# SwitchRouter2x3c.net
KiCad netlist of a schematic drawn in EAGLE
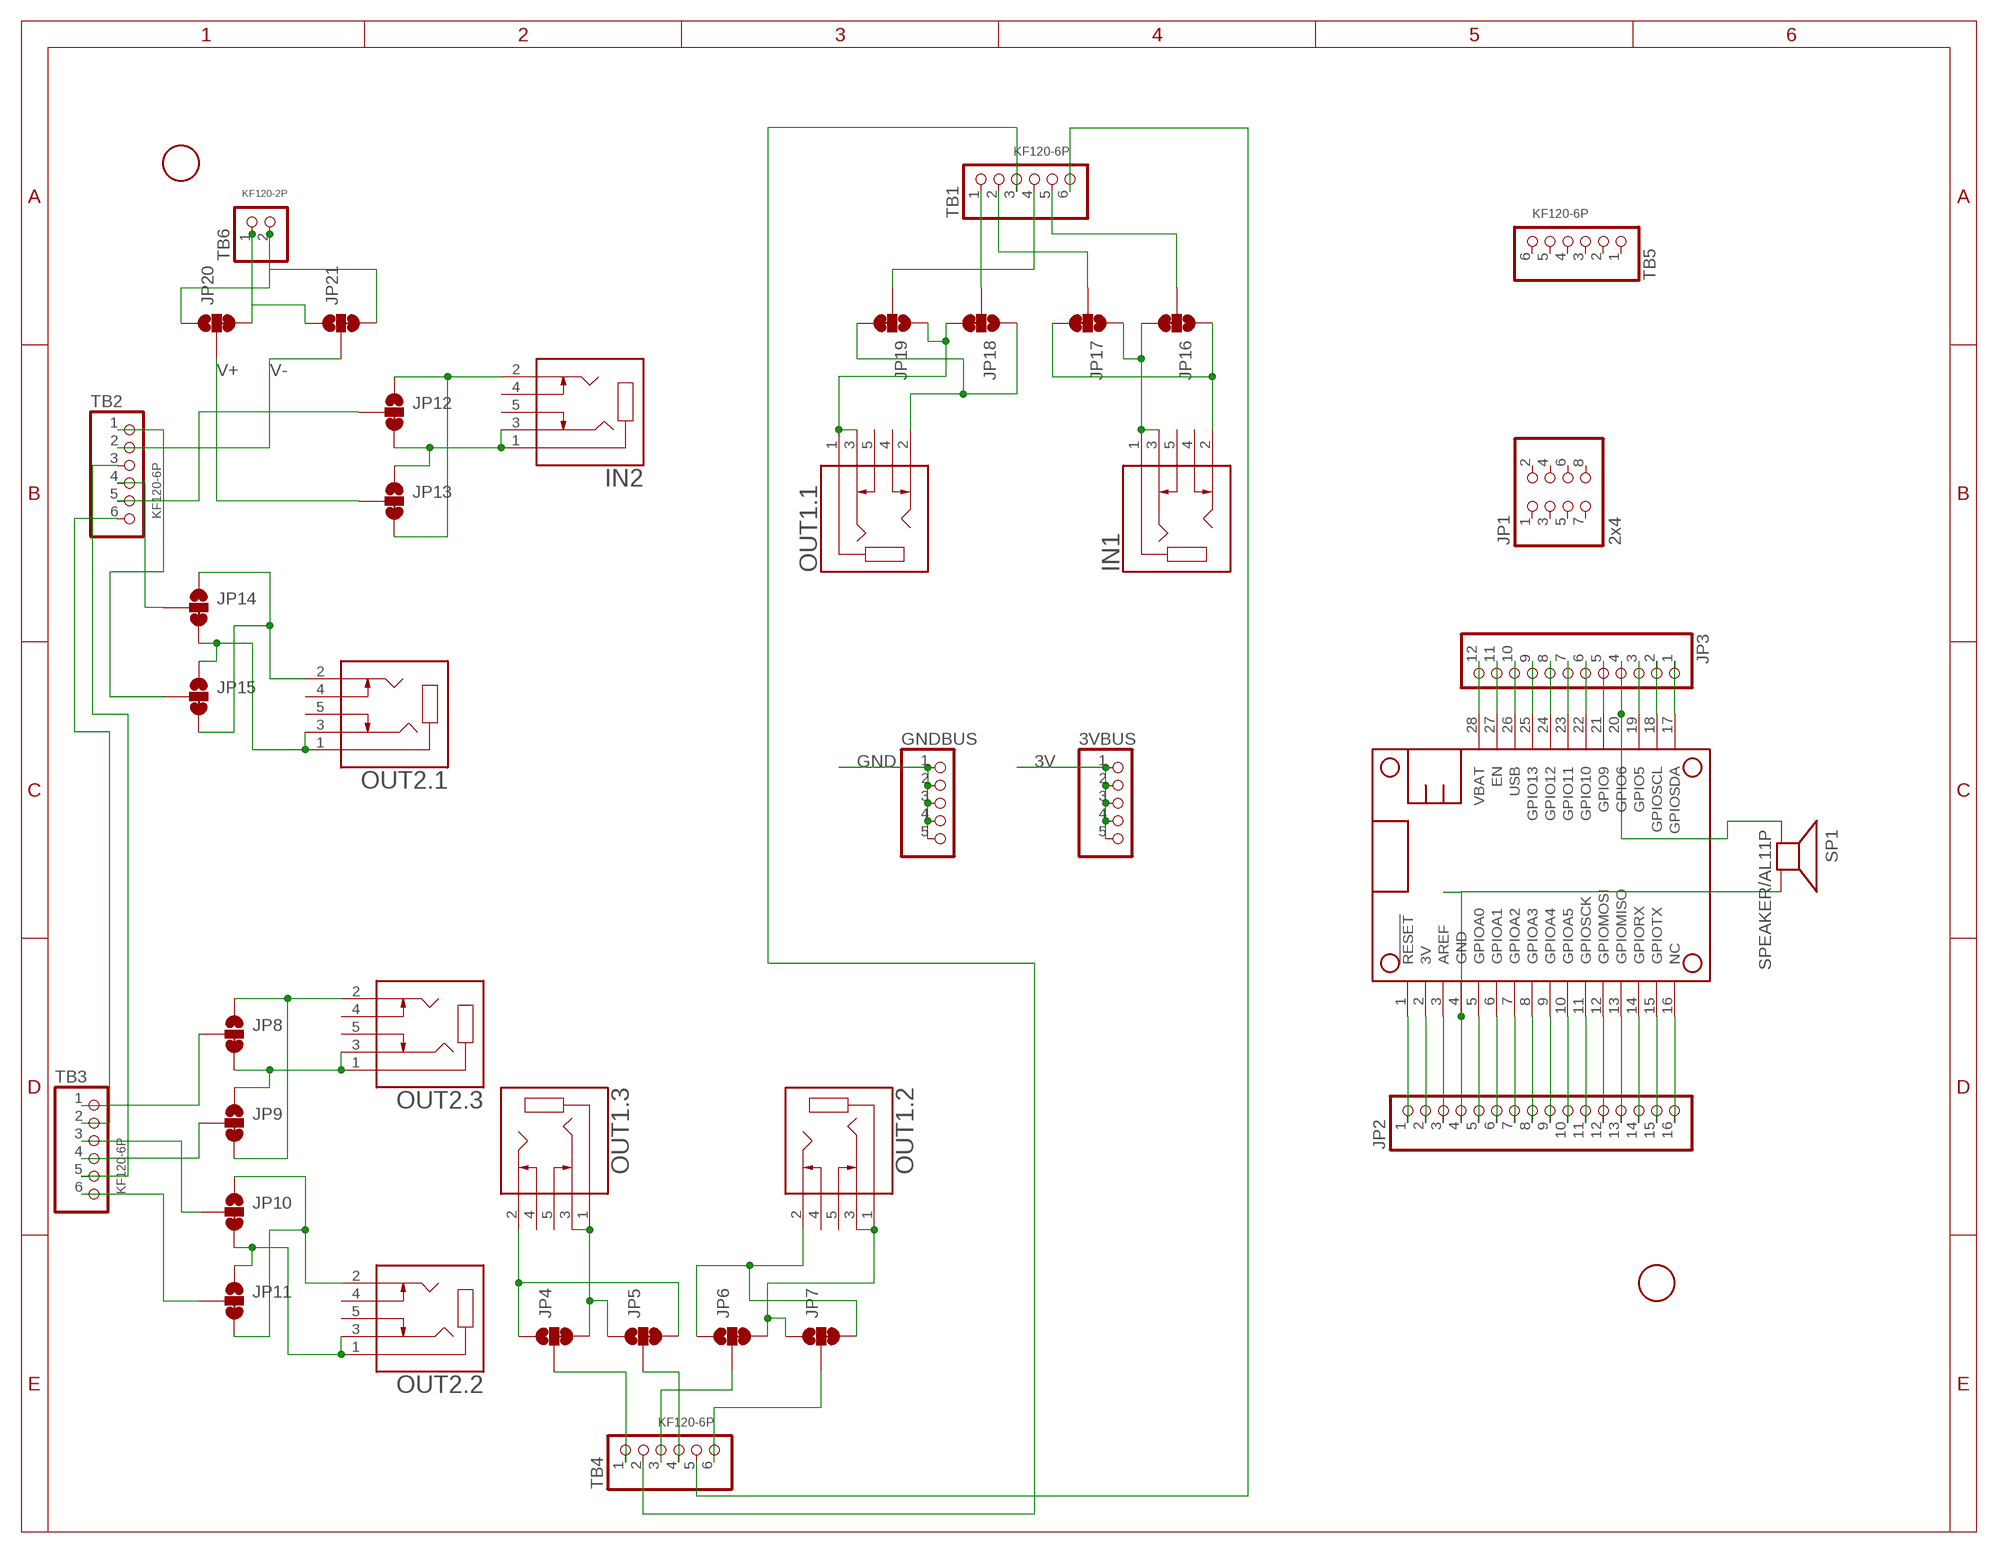
[diagram p0: schematic, sheet 1]

(export (version "E")
  (design (tool "Eeschema 10.0.6"))
  (components
    (comp (ref "3VBUS")
      (value "PINHD-1X55X2MM")
      (footprint "eagle-import:1_05X2MM")
      (libsource (lib "eagle-import") (part "PINHD-1X55X2MM"))
    )
    (comp (ref "GNDBUS")
      (value "PINHD-1X55X2MM")
      (footprint "eagle-import:1_05X2MM")
      (libsource (lib "eagle-import") (part "PINHD-1X55X2MM"))
    )
    (comp (ref "IN1")
      (value "SJ1-3535NG-PI")
      (footprint "eagle-import:CUI_SJ1-3535NG-PI")
      (fields (field (name "MANUFACTURER") "CUI"))
      (libsource (lib "eagle-import") (part "SJ1-3535NG-PI"))
    )
    (comp (ref "IN2")
      (value "SJ1-3535NG-PI")
      (footprint "eagle-import:CUI_SJ1-3535NG-PI")
      (fields (field (name "MANUFACTURER") "CUI"))
      (libsource (lib "eagle-import") (part "SJ1-3535NG-PI"))
    )
    (comp (ref "JP1")
      (value "2x4")
      (footprint "eagle-import:2X04")
      (libsource (lib "eagle-import") (part "PINHD-2X4"))
    )
    (comp (ref "JP2")
      (value "PINHD-1X16")
      (footprint "eagle-import:1X16")
      (libsource (lib "eagle-import") (part "PINHD-1X16"))
    )
    (comp (ref "JP3")
      (value "PINHD-1X12")
      (footprint "eagle-import:1X12")
      (libsource (lib "eagle-import") (part "PINHD-1X12"))
    )
    (comp (ref "JP4")
      (value "JUMPER-SMT_3_1-NC_TRACE_SILK")
      (footprint "eagle-import:SMT-JUMPER_3_1-NC_TRACE_SILK")
      (libsource (lib "eagle-import") (part "JUMPER-SMT_3_1-NC_TRACE_SILK"))
    )
    (comp (ref "JP5")
      (value "JUMPER-SMT_3_1-NC_TRACE_SILK")
      (footprint "eagle-import:SMT-JUMPER_3_1-NC_TRACE_SILK")
      (libsource (lib "eagle-import") (part "JUMPER-SMT_3_1-NC_TRACE_SILK"))
    )
    (comp (ref "JP6")
      (value "JUMPER-SMT_3_1-NC_TRACE_SILK")
      (footprint "eagle-import:SMT-JUMPER_3_1-NC_TRACE_SILK")
      (libsource (lib "eagle-import") (part "JUMPER-SMT_3_1-NC_TRACE_SILK"))
    )
    (comp (ref "JP7")
      (value "JUMPER-SMT_3_1-NC_TRACE_SILK")
      (footprint "eagle-import:SMT-JUMPER_3_1-NC_TRACE_SILK")
      (libsource (lib "eagle-import") (part "JUMPER-SMT_3_1-NC_TRACE_SILK"))
    )
    (comp (ref "JP8")
      (value "JUMPER-SMT_3_1-NC_TRACE_SILK")
      (footprint "eagle-import:SMT-JUMPER_3_1-NC_TRACE_SILK")
      (libsource (lib "eagle-import") (part "JUMPER-SMT_3_1-NC_TRACE_SILK"))
    )
    (comp (ref "JP9")
      (value "JUMPER-SMT_3_1-NC_TRACE_SILK")
      (footprint "eagle-import:SMT-JUMPER_3_1-NC_TRACE_SILK")
      (libsource (lib "eagle-import") (part "JUMPER-SMT_3_1-NC_TRACE_SILK"))
    )
    (comp (ref "JP10")
      (value "JUMPER-SMT_3_1-NC_TRACE_SILK")
      (footprint "eagle-import:SMT-JUMPER_3_1-NC_TRACE_SILK")
      (libsource (lib "eagle-import") (part "JUMPER-SMT_3_1-NC_TRACE_SILK"))
    )
    (comp (ref "JP11")
      (value "JUMPER-SMT_3_1-NC_TRACE_SILK")
      (footprint "eagle-import:SMT-JUMPER_3_1-NC_TRACE_SILK")
      (libsource (lib "eagle-import") (part "JUMPER-SMT_3_1-NC_TRACE_SILK"))
    )
    (comp (ref "JP12")
      (value "JUMPER-SMT_3_1-NC_TRACE_SILK")
      (footprint "eagle-import:SMT-JUMPER_3_1-NC_TRACE_SILK")
      (libsource (lib "eagle-import") (part "JUMPER-SMT_3_1-NC_TRACE_SILK"))
    )
    (comp (ref "JP13")
      (value "JUMPER-SMT_3_1-NC_TRACE_SILK")
      (footprint "eagle-import:SMT-JUMPER_3_1-NC_TRACE_SILK")
      (libsource (lib "eagle-import") (part "JUMPER-SMT_3_1-NC_TRACE_SILK"))
    )
    (comp (ref "JP14")
      (value "JUMPER-SMT_3_1-NC_TRACE_SILK")
      (footprint "eagle-import:SMT-JUMPER_3_1-NC_TRACE_SILK")
      (libsource (lib "eagle-import") (part "JUMPER-SMT_3_1-NC_TRACE_SILK"))
    )
    (comp (ref "JP15")
      (value "JUMPER-SMT_3_1-NC_TRACE_SILK")
      (footprint "eagle-import:SMT-JUMPER_3_1-NC_TRACE_SILK")
      (libsource (lib "eagle-import") (part "JUMPER-SMT_3_1-NC_TRACE_SILK"))
    )
    (comp (ref "JP16")
      (value "JUMPER-SMT_3_1-NC_TRACE_SILK")
      (footprint "eagle-import:SMT-JUMPER_3_1-NC_TRACE_SILK")
      (libsource (lib "eagle-import") (part "JUMPER-SMT_3_1-NC_TRACE_SILK"))
    )
    (comp (ref "JP17")
      (value "JUMPER-SMT_3_1-NC_TRACE_SILK")
      (footprint "eagle-import:SMT-JUMPER_3_1-NC_TRACE_SILK")
      (libsource (lib "eagle-import") (part "JUMPER-SMT_3_1-NC_TRACE_SILK"))
    )
    (comp (ref "JP18")
      (value "JUMPER-SMT_3_1-NC_TRACE_SILK")
      (footprint "eagle-import:SMT-JUMPER_3_1-NC_TRACE_SILK")
      (libsource (lib "eagle-import") (part "JUMPER-SMT_3_1-NC_TRACE_SILK"))
    )
    (comp (ref "JP19")
      (value "JUMPER-SMT_3_1-NC_TRACE_SILK")
      (footprint "eagle-import:SMT-JUMPER_3_1-NC_TRACE_SILK")
      (libsource (lib "eagle-import") (part "JUMPER-SMT_3_1-NC_TRACE_SILK"))
    )
    (comp (ref "JP20")
      (value "JUMPER-SMT_3_1-NC_TRACE_SILK")
      (footprint "eagle-import:SMT-JUMPER_3_1-NC_TRACE_SILK")
      (libsource (lib "eagle-import") (part "JUMPER-SMT_3_1-NC_TRACE_SILK"))
    )
    (comp (ref "JP21")
      (value "JUMPER-SMT_3_1-NC_TRACE_SILK")
      (footprint "eagle-import:SMT-JUMPER_3_1-NC_TRACE_SILK")
      (libsource (lib "eagle-import") (part "JUMPER-SMT_3_1-NC_TRACE_SILK"))
    )
    (comp (ref "MS1")
      (value "FEATHERWING_NODIM")
      (footprint "eagle-import:FEATHERWING_DIM")
      (libsource (lib "eagle-import") (part "FEATHERWING_NODIM"))
    )
    (comp (ref "OUT1.1")
      (value "SJ1-3535NG-PI")
      (footprint "eagle-import:CUI_SJ1-3535NG-PI")
      (fields (field (name "MANUFACTURER") "CUI"))
      (libsource (lib "eagle-import") (part "SJ1-3535NG-PI"))
    )
    (comp (ref "OUT1.2")
      (value "SJ1-3535NG-PI")
      (footprint "eagle-import:CUI_SJ1-3535NG-PI")
      (fields (field (name "MANUFACTURER") "CUI"))
      (libsource (lib "eagle-import") (part "SJ1-3535NG-PI"))
    )
    (comp (ref "OUT1.3")
      (value "SJ1-3535NG-PI")
      (footprint "eagle-import:CUI_SJ1-3535NG-PI")
      (fields (field (name "MANUFACTURER") "CUI"))
      (libsource (lib "eagle-import") (part "SJ1-3535NG-PI"))
    )
    (comp (ref "OUT2.1")
      (value "SJ1-3535NG-PI")
      (footprint "eagle-import:CUI_SJ1-3535NG-PI")
      (fields (field (name "MANUFACTURER") "CUI"))
      (libsource (lib "eagle-import") (part "SJ1-3535NG-PI"))
    )
    (comp (ref "OUT2.2")
      (value "SJ1-3535NG-PI")
      (footprint "eagle-import:CUI_SJ1-3535NG-PI")
      (fields (field (name "MANUFACTURER") "CUI"))
      (libsource (lib "eagle-import") (part "SJ1-3535NG-PI"))
    )
    (comp (ref "OUT2.3")
      (value "SJ1-3535NG-PI")
      (footprint "eagle-import:CUI_SJ1-3535NG-PI")
      (fields (field (name "MANUFACTURER") "CUI"))
      (libsource (lib "eagle-import") (part "SJ1-3535NG-PI"))
    )
    (comp (ref "SP1")
      (value "SPEAKER/AL11P")
      (footprint "eagle-import:AL11P")
      (libsource (lib "eagle-import") (part "SPEAKER/AL11P"))
    )
    (comp (ref "TB1")
      (value "KF120-6P")
      (footprint "eagle-import:KF120-6P_ROUND")
      (libsource (lib "eagle-import") (part "KF120-6P"))
    )
    (comp (ref "TB2")
      (value "KF120-6P")
      (footprint "eagle-import:KF120-6P_ROUND")
      (libsource (lib "eagle-import") (part "KF120-6P"))
    )
    (comp (ref "TB3")
      (value "KF120-6P")
      (footprint "eagle-import:KF120-6P_ROUND")
      (libsource (lib "eagle-import") (part "KF120-6P"))
    )
    (comp (ref "TB4")
      (value "KF120-6P")
      (footprint "eagle-import:KF120-6P_ROUND")
      (libsource (lib "eagle-import") (part "KF120-6P"))
    )
    (comp (ref "TB5")
      (value "KF120-6P")
      (footprint "eagle-import:KF120-6P_ROUND")
      (libsource (lib "eagle-import") (part "KF120-6P"))
    )
    (comp (ref "TB6")
      (value "KF120-2P")
      (footprint "eagle-import:KF120-2P_ROUND")
      (libsource (lib "eagle-import") (part "KF120-2P"))
    )
    (comp (ref "U$2")
      (value "FIDUCIAL")
      (footprint "eagle-import:FIDUCIAL_1MM")
      (libsource (lib "eagle-import") (part "FIDUCIAL"))
    )
    (comp (ref "U$3")
      (value "FIDUCIAL")
      (footprint "eagle-import:FIDUCIAL_1MM")
      (libsource (lib "eagle-import") (part "FIDUCIAL"))
    )
  )
  (nets
    (net (code "1") (name "/3V") (class "Default")
      (node (ref "3VBUS") (pin "1") (pinfunction "1_1") (pintype "passive"))
      (node (ref "3VBUS") (pin "2") (pinfunction "2_2") (pintype "passive"))
      (node (ref "3VBUS") (pin "3") (pinfunction "3_3") (pintype "passive"))
      (node (ref "3VBUS") (pin "4") (pinfunction "4_4") (pintype "passive"))
      (node (ref "3VBUS") (pin "5") (pinfunction "5_5") (pintype "passive"))
      (node (ref "JP2") (pin "2") (pinfunction "2_2") (pintype "passive"))
      (node (ref "MS1") (pin "2") (pinfunction "3V_2") (pintype "power_in"))
    )
    (net (code "2") (name "/GND") (class "Default")
      (node (ref "GNDBUS") (pin "1") (pinfunction "1_1") (pintype "passive"))
      (node (ref "GNDBUS") (pin "2") (pinfunction "2_2") (pintype "passive"))
      (node (ref "GNDBUS") (pin "3") (pinfunction "3_3") (pintype "passive"))
      (node (ref "GNDBUS") (pin "4") (pinfunction "4_4") (pintype "passive"))
      (node (ref "GNDBUS") (pin "5") (pinfunction "5_5") (pintype "passive"))
      (node (ref "JP2") (pin "4") (pinfunction "4_4") (pintype "passive"))
      (node (ref "MS1") (pin "4") (pinfunction "GND_4") (pintype "power_in"))
      (node (ref "SP1") (pin "-") (pinfunction "-_-") (pintype "passive"))
    )
    (net (code "3") (name "/V+") (class "Default")
      (node (ref "JP13") (pin "2") (pinfunction "2_2") (pintype "passive"))
      (node (ref "JP20") (pin "2") (pinfunction "2_2") (pintype "passive"))
    )
    (net (code "4") (name "/V-") (class "Default")
      (node (ref "JP21") (pin "2") (pinfunction "2_2") (pintype "passive"))
      (node (ref "TB2") (pin "2") (pinfunction "2_2") (pintype "passive"))
    )
    (net (code "5") (name "Net-(IN1-Pad1)") (class "Default")
      (node (ref "IN1") (pin "1") (pinfunction "1_1") (pintype "passive"))
      (node (ref "IN1") (pin "3") (pinfunction "3_3") (pintype "passive"))
      (node (ref "JP16") (pin "3") (pinfunction "3_3") (pintype "passive"))
      (node (ref "JP17") (pin "1") (pinfunction "1_1") (pintype "passive"))
    )
    (net (code "6") (name "Net-(IN1-Pad2)") (class "Default")
      (node (ref "IN1") (pin "2") (pinfunction "2_2") (pintype "passive"))
      (node (ref "JP16") (pin "1") (pinfunction "1_1") (pintype "passive"))
      (node (ref "JP17") (pin "3") (pinfunction "3_3") (pintype "passive"))
    )
    (net (code "7") (name "Net-(IN2-Pad1)") (class "Default")
      (node (ref "IN2") (pin "1") (pinfunction "1_1") (pintype "passive"))
      (node (ref "IN2") (pin "3") (pinfunction "3_3") (pintype "passive"))
      (node (ref "JP12") (pin "3") (pinfunction "3_3") (pintype "passive"))
      (node (ref "JP13") (pin "1") (pinfunction "1_1") (pintype "passive"))
    )
    (net (code "8") (name "Net-(IN2-Pad2)") (class "Default")
      (node (ref "IN2") (pin "2") (pinfunction "2_2") (pintype "passive"))
      (node (ref "JP12") (pin "1") (pinfunction "1_1") (pintype "passive"))
      (node (ref "JP13") (pin "3") (pinfunction "3_3") (pintype "passive"))
    )
    (net (code "9") (name "Net-(JP4-Pad1)") (class "Default")
      (node (ref "JP4") (pin "1") (pinfunction "1_1") (pintype "passive"))
      (node (ref "JP5") (pin "3") (pinfunction "3_3") (pintype "passive"))
      (node (ref "OUT1.3") (pin "2") (pinfunction "2_2") (pintype "passive"))
    )
    (net (code "10") (name "Net-(JP4-Pad2)") (class "Default")
      (node (ref "JP4") (pin "2") (pinfunction "2_2") (pintype "passive"))
      (node (ref "TB4") (pin "1") (pinfunction "1_1") (pintype "passive"))
    )
    (net (code "11") (name "Net-(JP4-Pad3)") (class "Default")
      (node (ref "JP4") (pin "3") (pinfunction "3_3") (pintype "passive"))
      (node (ref "JP5") (pin "1") (pinfunction "1_1") (pintype "passive"))
      (node (ref "OUT1.3") (pin "1") (pinfunction "1_1") (pintype "passive"))
      (node (ref "OUT1.3") (pin "3") (pinfunction "3_3") (pintype "passive"))
    )
    (net (code "12") (name "Net-(JP5-Pad2)") (class "Default")
      (node (ref "JP5") (pin "2") (pinfunction "2_2") (pintype "passive"))
      (node (ref "TB4") (pin "4") (pinfunction "4_4") (pintype "passive"))
    )
    (net (code "13") (name "Net-(JP6-Pad1)") (class "Default")
      (node (ref "JP6") (pin "1") (pinfunction "1_1") (pintype "passive"))
      (node (ref "JP7") (pin "3") (pinfunction "3_3") (pintype "passive"))
      (node (ref "OUT1.2") (pin "2") (pinfunction "2_2") (pintype "passive"))
    )
    (net (code "14") (name "Net-(JP6-Pad2)") (class "Default")
      (node (ref "JP6") (pin "2") (pinfunction "2_2") (pintype "passive"))
      (node (ref "TB4") (pin "3") (pinfunction "3_3") (pintype "passive"))
    )
    (net (code "15") (name "Net-(JP6-Pad3)") (class "Default")
      (node (ref "JP6") (pin "3") (pinfunction "3_3") (pintype "passive"))
      (node (ref "JP7") (pin "1") (pinfunction "1_1") (pintype "passive"))
      (node (ref "OUT1.2") (pin "1") (pinfunction "1_1") (pintype "passive"))
      (node (ref "OUT1.2") (pin "3") (pinfunction "3_3") (pintype "passive"))
    )
    (net (code "16") (name "Net-(JP7-Pad2)") (class "Default")
      (node (ref "JP7") (pin "2") (pinfunction "2_2") (pintype "passive"))
      (node (ref "TB4") (pin "6") (pinfunction "6_6") (pintype "passive"))
    )
    (net (code "17") (name "Net-(JP8-Pad1)") (class "Default")
      (node (ref "JP8") (pin "1") (pinfunction "1_1") (pintype "passive"))
      (node (ref "JP9") (pin "3") (pinfunction "3_3") (pintype "passive"))
      (node (ref "OUT2.3") (pin "2") (pinfunction "2_2") (pintype "passive"))
    )
    (net (code "18") (name "Net-(JP8-Pad2)") (class "Default")
      (node (ref "JP8") (pin "2") (pinfunction "2_2") (pintype "passive"))
      (node (ref "TB3") (pin "1") (pinfunction "1_1") (pintype "passive"))
    )
    (net (code "19") (name "Net-(JP8-Pad3)") (class "Default")
      (node (ref "JP8") (pin "3") (pinfunction "3_3") (pintype "passive"))
      (node (ref "JP9") (pin "1") (pinfunction "1_1") (pintype "passive"))
      (node (ref "OUT2.3") (pin "1") (pinfunction "1_1") (pintype "passive"))
      (node (ref "OUT2.3") (pin "3") (pinfunction "3_3") (pintype "passive"))
    )
    (net (code "20") (name "Net-(JP9-Pad2)") (class "Default")
      (node (ref "JP9") (pin "2") (pinfunction "2_2") (pintype "passive"))
      (node (ref "TB3") (pin "4") (pinfunction "4_4") (pintype "passive"))
    )
    (net (code "21") (name "Net-(JP10-Pad1)") (class "Default")
      (node (ref "JP10") (pin "1") (pinfunction "1_1") (pintype "passive"))
      (node (ref "JP11") (pin "3") (pinfunction "3_3") (pintype "passive"))
      (node (ref "OUT2.2") (pin "2") (pinfunction "2_2") (pintype "passive"))
    )
    (net (code "22") (name "Net-(JP10-Pad2)") (class "Default")
      (node (ref "JP10") (pin "2") (pinfunction "2_2") (pintype "passive"))
      (node (ref "TB3") (pin "3") (pinfunction "3_3") (pintype "passive"))
    )
    (net (code "23") (name "Net-(JP10-Pad3)") (class "Default")
      (node (ref "JP10") (pin "3") (pinfunction "3_3") (pintype "passive"))
      (node (ref "JP11") (pin "1") (pinfunction "1_1") (pintype "passive"))
      (node (ref "OUT2.2") (pin "1") (pinfunction "1_1") (pintype "passive"))
      (node (ref "OUT2.2") (pin "3") (pinfunction "3_3") (pintype "passive"))
    )
    (net (code "24") (name "Net-(JP11-Pad2)") (class "Default")
      (node (ref "JP11") (pin "2") (pinfunction "2_2") (pintype "passive"))
      (node (ref "TB3") (pin "6") (pinfunction "6_6") (pintype "passive"))
    )
    (net (code "25") (name "Net-(JP12-Pad2)") (class "Default")
      (node (ref "JP12") (pin "2") (pinfunction "2_2") (pintype "passive"))
      (node (ref "TB2") (pin "5") (pinfunction "5_5") (pintype "passive"))
    )
    (net (code "26") (name "Net-(JP14-Pad1)") (class "Default")
      (node (ref "JP14") (pin "1") (pinfunction "1_1") (pintype "passive"))
      (node (ref "JP15") (pin "3") (pinfunction "3_3") (pintype "passive"))
      (node (ref "OUT2.1") (pin "2") (pinfunction "2_2") (pintype "passive"))
    )
    (net (code "27") (name "Net-(JP14-Pad2)") (class "Default")
      (node (ref "JP14") (pin "2") (pinfunction "2_2") (pintype "passive"))
      (node (ref "TB2") (pin "4") (pinfunction "4_4") (pintype "passive"))
    )
    (net (code "28") (name "Net-(JP14-Pad3)") (class "Default")
      (node (ref "JP14") (pin "3") (pinfunction "3_3") (pintype "passive"))
      (node (ref "JP15") (pin "1") (pinfunction "1_1") (pintype "passive"))
      (node (ref "OUT2.1") (pin "1") (pinfunction "1_1") (pintype "passive"))
      (node (ref "OUT2.1") (pin "3") (pinfunction "3_3") (pintype "passive"))
    )
    (net (code "29") (name "Net-(JP15-Pad2)") (class "Default")
      (node (ref "JP15") (pin "2") (pinfunction "2_2") (pintype "passive"))
      (node (ref "TB2") (pin "1") (pinfunction "1_1") (pintype "passive"))
    )
    (net (code "30") (name "Net-(JP16-Pad2)") (class "Default")
      (node (ref "JP16") (pin "2") (pinfunction "2_2") (pintype "passive"))
      (node (ref "TB1") (pin "5") (pinfunction "5_5") (pintype "passive"))
    )
    (net (code "31") (name "Net-(JP17-Pad2)") (class "Default")
      (node (ref "JP17") (pin "2") (pinfunction "2_2") (pintype "passive"))
      (node (ref "TB1") (pin "2") (pinfunction "2_2") (pintype "passive"))
    )
    (net (code "32") (name "Net-(JP18-Pad1)") (class "Default")
      (node (ref "JP18") (pin "1") (pinfunction "1_1") (pintype "passive"))
      (node (ref "JP19") (pin "3") (pinfunction "3_3") (pintype "passive"))
      (node (ref "OUT1.1") (pin "2") (pinfunction "2_2") (pintype "passive"))
    )
    (net (code "33") (name "Net-(JP18-Pad2)") (class "Default")
      (node (ref "JP18") (pin "2") (pinfunction "2_2") (pintype "passive"))
      (node (ref "TB1") (pin "1") (pinfunction "1_1") (pintype "passive"))
    )
    (net (code "34") (name "Net-(JP18-Pad3)") (class "Default")
      (node (ref "JP18") (pin "3") (pinfunction "3_3") (pintype "passive"))
      (node (ref "JP19") (pin "1") (pinfunction "1_1") (pintype "passive"))
      (node (ref "OUT1.1") (pin "1") (pinfunction "1_1") (pintype "passive"))
      (node (ref "OUT1.1") (pin "3") (pinfunction "3_3") (pintype "passive"))
    )
    (net (code "35") (name "Net-(JP19-Pad2)") (class "Default")
      (node (ref "JP19") (pin "2") (pinfunction "2_2") (pintype "passive"))
      (node (ref "TB1") (pin "4") (pinfunction "4_4") (pintype "passive"))
    )
    (net (code "36") (name "Net-(JP20-Pad1)") (class "Default")
      (node (ref "JP20") (pin "1") (pinfunction "1_1") (pintype "passive"))
      (node (ref "JP21") (pin "3") (pinfunction "3_3") (pintype "passive"))
      (node (ref "TB6") (pin "2") (pinfunction "2_2") (pintype "passive"))
    )
    (net (code "37") (name "Net-(JP20-Pad3)") (class "Default")
      (node (ref "JP20") (pin "3") (pinfunction "3_3") (pintype "passive"))
      (node (ref "JP21") (pin "1") (pinfunction "1_1") (pintype "passive"))
      (node (ref "TB6") (pin "1") (pinfunction "1_1") (pintype "passive"))
    )
    (net (code "38") (name "Net-(MS1-AREF)") (class "Default")
      (node (ref "JP2") (pin "3") (pinfunction "3_3") (pintype "passive"))
      (node (ref "MS1") (pin "3") (pinfunction "AREF_3") (pintype "passive"))
    )
    (net (code "39") (name "Net-(MS1-EN)") (class "Default")
      (node (ref "JP3") (pin "11") (pinfunction "11_11") (pintype "passive"))
      (node (ref "MS1") (pin "27") (pinfunction "EN_27") (pintype "passive"))
    )
    (net (code "40") (name "Net-(MS1-GPIO5)") (class "Default")
      (node (ref "JP3") (pin "3") (pinfunction "3_3") (pintype "passive"))
      (node (ref "MS1") (pin "19") (pinfunction "GPIO5_19") (pintype "bidirectional"))
    )
    (net (code "41") (name "Net-(MS1-GPIO6)") (class "Default")
      (node (ref "JP3") (pin "4") (pinfunction "4_4") (pintype "passive"))
      (node (ref "MS1") (pin "20") (pinfunction "GPIO6_20") (pintype "bidirectional"))
      (node (ref "SP1") (pin "+") (pinfunction "+_+") (pintype "passive"))
    )
    (net (code "42") (name "Net-(MS1-GPIO9)") (class "Default")
      (node (ref "JP3") (pin "5") (pinfunction "5_5") (pintype "passive"))
      (node (ref "MS1") (pin "21") (pinfunction "GPIO9_21") (pintype "bidirectional"))
    )
    (net (code "43") (name "Net-(MS1-GPIO10)") (class "Default")
      (node (ref "JP3") (pin "6") (pinfunction "6_6") (pintype "passive"))
      (node (ref "MS1") (pin "22") (pinfunction "GPIO10_22") (pintype "bidirectional"))
    )
    (net (code "44") (name "Net-(MS1-GPIO11)") (class "Default")
      (node (ref "JP3") (pin "7") (pinfunction "7_7") (pintype "passive"))
      (node (ref "MS1") (pin "23") (pinfunction "GPIO11_23") (pintype "bidirectional"))
    )
    (net (code "45") (name "Net-(MS1-GPIO12)") (class "Default")
      (node (ref "JP3") (pin "8") (pinfunction "8_8") (pintype "passive"))
      (node (ref "MS1") (pin "24") (pinfunction "GPIO12_24") (pintype "bidirectional"))
    )
    (net (code "46") (name "Net-(MS1-GPIO13)") (class "Default")
      (node (ref "JP3") (pin "9") (pinfunction "9_9") (pintype "passive"))
      (node (ref "MS1") (pin "25") (pinfunction "GPIO13_25") (pintype "bidirectional"))
    )
    (net (code "47") (name "Net-(MS1-GPIOA0)") (class "Default")
      (node (ref "JP2") (pin "5") (pinfunction "5_5") (pintype "passive"))
      (node (ref "MS1") (pin "5") (pinfunction "GPIOA0_5") (pintype "bidirectional"))
    )
    (net (code "48") (name "Net-(MS1-GPIOA1)") (class "Default")
      (node (ref "JP2") (pin "6") (pinfunction "6_6") (pintype "passive"))
      (node (ref "MS1") (pin "6") (pinfunction "GPIOA1_6") (pintype "bidirectional"))
    )
    (net (code "49") (name "Net-(MS1-GPIOA2)") (class "Default")
      (node (ref "JP2") (pin "7") (pinfunction "7_7") (pintype "passive"))
      (node (ref "MS1") (pin "7") (pinfunction "GPIOA2_7") (pintype "bidirectional"))
    )
    (net (code "50") (name "Net-(MS1-GPIOA3)") (class "Default")
      (node (ref "JP2") (pin "8") (pinfunction "8_8") (pintype "passive"))
      (node (ref "MS1") (pin "8") (pinfunction "GPIOA3_8") (pintype "bidirectional"))
    )
    (net (code "51") (name "Net-(MS1-GPIOA4)") (class "Default")
      (node (ref "JP2") (pin "9") (pinfunction "9_9") (pintype "passive"))
      (node (ref "MS1") (pin "9") (pinfunction "GPIOA4_9") (pintype "bidirectional"))
    )
    (net (code "52") (name "Net-(MS1-GPIOA5)") (class "Default")
      (node (ref "JP2") (pin "10") (pinfunction "10_10") (pintype "passive"))
      (node (ref "MS1") (pin "10") (pinfunction "GPIOA5_10") (pintype "bidirectional"))
    )
    (net (code "53") (name "Net-(MS1-GPIOMISO)") (class "Default")
      (node (ref "JP2") (pin "13") (pinfunction "13_13") (pintype "passive"))
      (node (ref "MS1") (pin "13") (pinfunction "GPIOMISO_13") (pintype "bidirectional"))
    )
    (net (code "54") (name "Net-(MS1-GPIOMOSI)") (class "Default")
      (node (ref "JP2") (pin "12") (pinfunction "12_12") (pintype "passive"))
      (node (ref "MS1") (pin "12") (pinfunction "GPIOMOSI_12") (pintype "bidirectional"))
    )
    (net (code "55") (name "Net-(MS1-GPIORX)") (class "Default")
      (node (ref "JP2") (pin "14") (pinfunction "14_14") (pintype "passive"))
      (node (ref "MS1") (pin "14") (pinfunction "GPIORX_14") (pintype "bidirectional"))
    )
    (net (code "56") (name "Net-(MS1-GPIOSCK)") (class "Default")
      (node (ref "JP2") (pin "11") (pinfunction "11_11") (pintype "passive"))
      (node (ref "MS1") (pin "11") (pinfunction "GPIOSCK_11") (pintype "bidirectional"))
    )
    (net (code "57") (name "Net-(MS1-GPIOSCL)") (class "Default")
      (node (ref "JP3") (pin "2") (pinfunction "2_2") (pintype "passive"))
      (node (ref "MS1") (pin "18") (pinfunction "GPIOSCL_18") (pintype "bidirectional"))
    )
    (net (code "58") (name "Net-(MS1-GPIOSDA)") (class "Default")
      (node (ref "JP3") (pin "1") (pinfunction "1_1") (pintype "passive"))
      (node (ref "MS1") (pin "17") (pinfunction "GPIOSDA_17") (pintype "bidirectional"))
    )
    (net (code "59") (name "Net-(MS1-GPIOTX)") (class "Default")
      (node (ref "JP2") (pin "15") (pinfunction "15_15") (pintype "passive"))
      (node (ref "MS1") (pin "15") (pinfunction "GPIOTX_15") (pintype "bidirectional"))
    )
    (net (code "60") (name "Net-(MS1-NC)") (class "Default")
      (node (ref "JP2") (pin "16") (pinfunction "16_16") (pintype "passive"))
      (node (ref "MS1") (pin "16") (pinfunction "NC_16") (pintype "passive"))
    )
    (net (code "61") (name "Net-(MS1-USB)") (class "Default")
      (node (ref "JP3") (pin "10") (pinfunction "10_10") (pintype "passive"))
      (node (ref "MS1") (pin "26") (pinfunction "USB_26") (pintype "power_in"))
    )
    (net (code "62") (name "Net-(MS1-VBAT)") (class "Default")
      (node (ref "JP3") (pin "12") (pinfunction "12_12") (pintype "passive"))
      (node (ref "MS1") (pin "28") (pinfunction "VBAT_28") (pintype "power_in"))
    )
    (net (code "63") (name "Net-(MS1-~{RESET})") (class "Default")
      (node (ref "JP2") (pin "1") (pinfunction "1_1") (pintype "passive"))
      (node (ref "MS1") (pin "1") (pinfunction "~{RESET}_1") (pintype "input"))
    )
    (net (code "64") (name "Net-(TB1-Pad3)") (class "Default")
      (node (ref "TB1") (pin "3") (pinfunction "3_3") (pintype "passive"))
      (node (ref "TB4") (pin "2") (pinfunction "2_2") (pintype "passive"))
    )
    (net (code "65") (name "Net-(TB1-Pad6)") (class "Default")
      (node (ref "TB1") (pin "6") (pinfunction "6_6") (pintype "passive"))
      (node (ref "TB4") (pin "5") (pinfunction "5_5") (pintype "passive"))
    )
    (net (code "66") (name "Net-(TB2-Pad3)") (class "Default")
      (node (ref "TB2") (pin "3") (pinfunction "3_3") (pintype "passive"))
      (node (ref "TB3") (pin "5") (pinfunction "5_5") (pintype "passive"))
    )
    (net (code "67") (name "Net-(TB2-Pad6)") (class "Default")
      (node (ref "TB2") (pin "6") (pinfunction "6_6") (pintype "passive"))
      (node (ref "TB3") (pin "2") (pinfunction "2_2") (pintype "passive"))
    )
    (net (code "68") (name "unconnected-(IN1-Pad4)") (class "Default")
      (node (ref "IN1") (pin "4") (pinfunction "4_4") (pintype "passive"))
    )
    (net (code "69") (name "unconnected-(IN1-Pad5)") (class "Default")
      (node (ref "IN1") (pin "5") (pinfunction "5_5") (pintype "passive"))
    )
    (net (code "70") (name "unconnected-(IN2-Pad4)") (class "Default")
      (node (ref "IN2") (pin "4") (pinfunction "4_4") (pintype "passive"))
    )
    (net (code "71") (name "unconnected-(IN2-Pad5)") (class "Default")
      (node (ref "IN2") (pin "5") (pinfunction "5_5") (pintype "passive"))
    )
    (net (code "72") (name "unconnected-(JP1-Pad1)") (class "Default")
      (node (ref "JP1") (pin "1") (pinfunction "1_1") (pintype "passive"))
    )
    (net (code "73") (name "unconnected-(JP1-Pad2)") (class "Default")
      (node (ref "JP1") (pin "2") (pinfunction "2_2") (pintype "passive"))
    )
    (net (code "74") (name "unconnected-(JP1-Pad3)") (class "Default")
      (node (ref "JP1") (pin "3") (pinfunction "3_3") (pintype "passive"))
    )
    (net (code "75") (name "unconnected-(JP1-Pad4)") (class "Default")
      (node (ref "JP1") (pin "4") (pinfunction "4_4") (pintype "passive"))
    )
    (net (code "76") (name "unconnected-(JP1-Pad5)") (class "Default")
      (node (ref "JP1") (pin "5") (pinfunction "5_5") (pintype "passive"))
    )
    (net (code "77") (name "unconnected-(JP1-Pad6)") (class "Default")
      (node (ref "JP1") (pin "6") (pinfunction "6_6") (pintype "passive"))
    )
    (net (code "78") (name "unconnected-(JP1-Pad7)") (class "Default")
      (node (ref "JP1") (pin "7") (pinfunction "7_7") (pintype "passive"))
    )
    (net (code "79") (name "unconnected-(JP1-Pad8)") (class "Default")
      (node (ref "JP1") (pin "8") (pinfunction "8_8") (pintype "passive"))
    )
    (net (code "80") (name "unconnected-(OUT1.1-Pad4)") (class "Default")
      (node (ref "OUT1.1") (pin "4") (pinfunction "4_4") (pintype "passive"))
    )
    (net (code "81") (name "unconnected-(OUT1.1-Pad5)") (class "Default")
      (node (ref "OUT1.1") (pin "5") (pinfunction "5_5") (pintype "passive"))
    )
    (net (code "82") (name "unconnected-(OUT1.2-Pad4)") (class "Default")
      (node (ref "OUT1.2") (pin "4") (pinfunction "4_4") (pintype "passive"))
    )
    (net (code "83") (name "unconnected-(OUT1.2-Pad5)") (class "Default")
      (node (ref "OUT1.2") (pin "5") (pinfunction "5_5") (pintype "passive"))
    )
    (net (code "84") (name "unconnected-(OUT1.3-Pad4)") (class "Default")
      (node (ref "OUT1.3") (pin "4") (pinfunction "4_4") (pintype "passive"))
    )
    (net (code "85") (name "unconnected-(OUT1.3-Pad5)") (class "Default")
      (node (ref "OUT1.3") (pin "5") (pinfunction "5_5") (pintype "passive"))
    )
    (net (code "86") (name "unconnected-(OUT2.1-Pad4)") (class "Default")
      (node (ref "OUT2.1") (pin "4") (pinfunction "4_4") (pintype "passive"))
    )
    (net (code "87") (name "unconnected-(OUT2.1-Pad5)") (class "Default")
      (node (ref "OUT2.1") (pin "5") (pinfunction "5_5") (pintype "passive"))
    )
    (net (code "88") (name "unconnected-(OUT2.2-Pad4)") (class "Default")
      (node (ref "OUT2.2") (pin "4") (pinfunction "4_4") (pintype "passive"))
    )
    (net (code "89") (name "unconnected-(OUT2.2-Pad5)") (class "Default")
      (node (ref "OUT2.2") (pin "5") (pinfunction "5_5") (pintype "passive"))
    )
    (net (code "90") (name "unconnected-(OUT2.3-Pad4)") (class "Default")
      (node (ref "OUT2.3") (pin "4") (pinfunction "4_4") (pintype "passive"))
    )
    (net (code "91") (name "unconnected-(OUT2.3-Pad5)") (class "Default")
      (node (ref "OUT2.3") (pin "5") (pinfunction "5_5") (pintype "passive"))
    )
    (net (code "92") (name "unconnected-(TB5-Pad1)") (class "Default")
      (node (ref "TB5") (pin "1") (pinfunction "1_1") (pintype "passive"))
    )
    (net (code "93") (name "unconnected-(TB5-Pad2)") (class "Default")
      (node (ref "TB5") (pin "2") (pinfunction "2_2") (pintype "passive"))
    )
    (net (code "94") (name "unconnected-(TB5-Pad3)") (class "Default")
      (node (ref "TB5") (pin "3") (pinfunction "3_3") (pintype "passive"))
    )
    (net (code "95") (name "unconnected-(TB5-Pad4)") (class "Default")
      (node (ref "TB5") (pin "4") (pinfunction "4_4") (pintype "passive"))
    )
    (net (code "96") (name "unconnected-(TB5-Pad5)") (class "Default")
      (node (ref "TB5") (pin "5") (pinfunction "5_5") (pintype "passive"))
    )
    (net (code "97") (name "unconnected-(TB5-Pad6)") (class "Default")
      (node (ref "TB5") (pin "6") (pinfunction "6_6") (pintype "passive"))
    )
  )
)
